# pcb.net
KiCad netlist of a schematic drawn in EAGLE
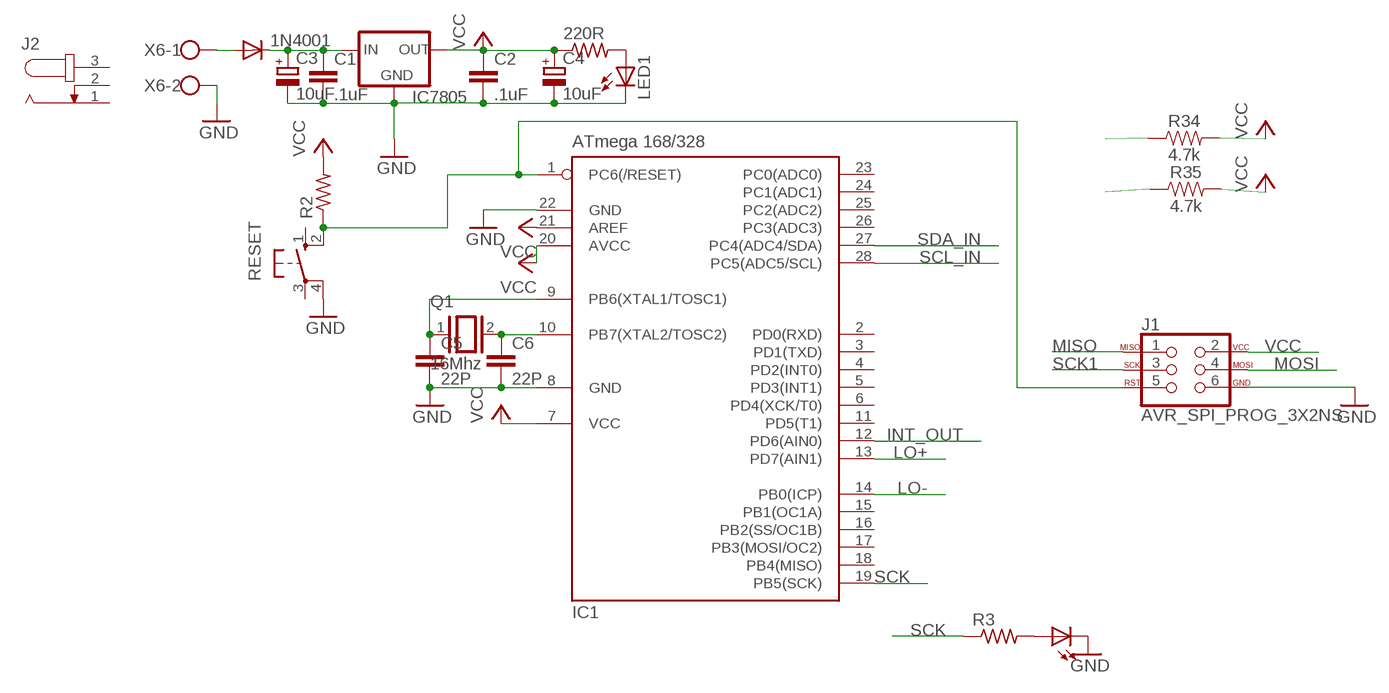
[diagram p0: schematic, sheet 1]
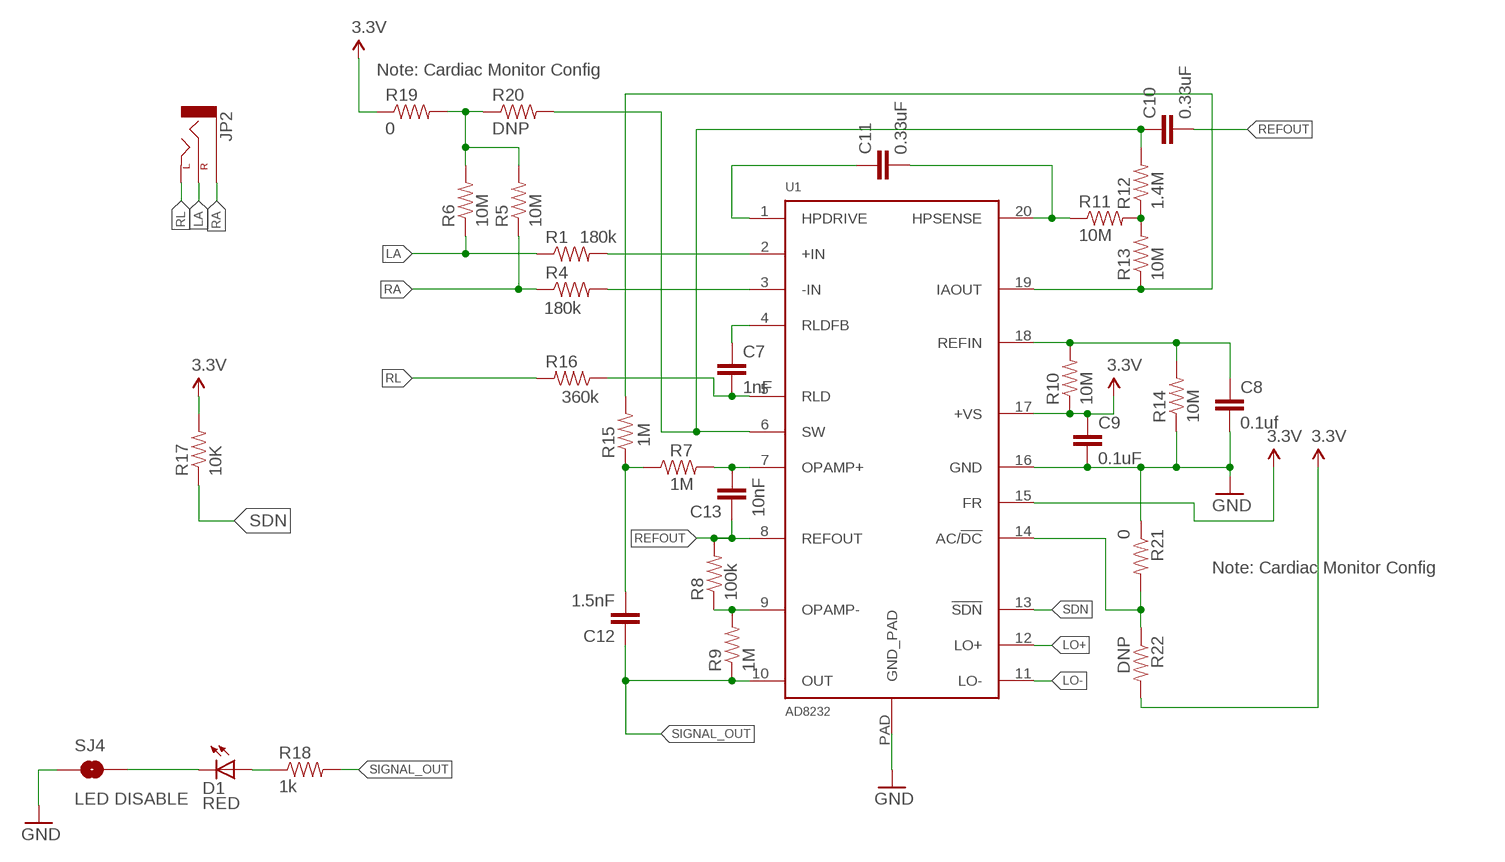
[diagram p1: schematic, sheet 2]
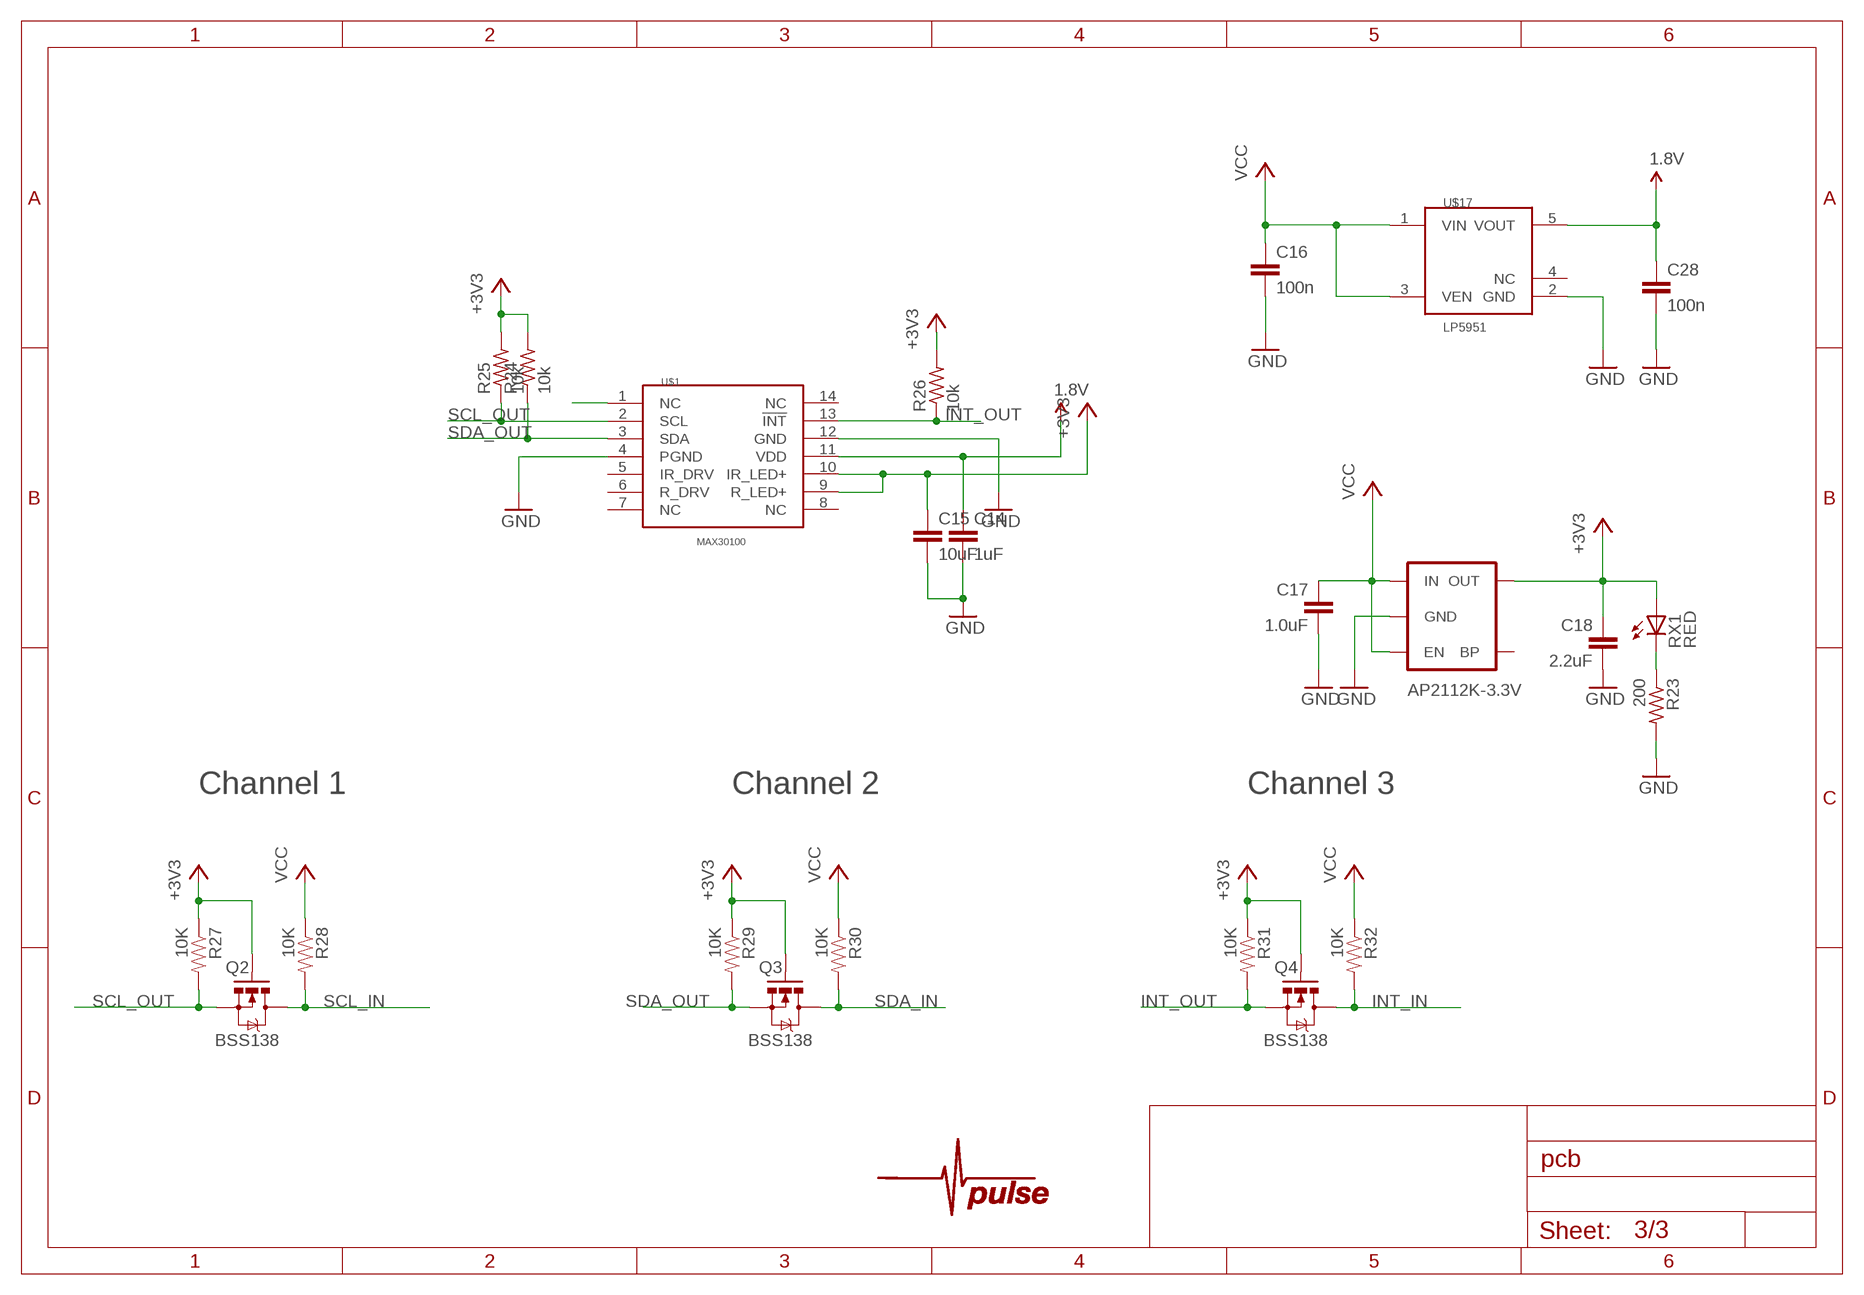
[diagram p2: schematic, sheet 3]

(export (version "E")
  (design (tool "Eeschema 10.0.6"))
  (components
    (comp (ref "C14")
      (value "1uF")
      (footprint "eagle-import:C0805")
      (libsource (lib "eagle-import") (part "C-EUC0805"))
    )
    (comp (ref "C15")
      (value "10uF")
      (footprint "eagle-import:C0805")
      (libsource (lib "eagle-import") (part "C-EUC0805"))
    )
    (comp (ref "C16")
      (value "100n")
      (footprint "eagle-import:C0402")
      (libsource (lib "eagle-import") (part "C-EUC0402"))
    )
    (comp (ref "C17")
      (value "1.0uF")
      (footprint "eagle-import:0805")
      (libsource (lib "eagle-import") (part "1.0UF-25V-+80/-20(0805)"))
    )
    (comp (ref "C18")
      (value "2.2uF")
      (footprint "eagle-import:C0805")
      (libsource (lib "eagle-import") (part "C-EUC0805"))
    )
    (comp (ref "C28")
      (value "100n")
      (footprint "eagle-import:C0402")
      (libsource (lib "eagle-import") (part "C-EUC0402"))
    )
    (comp (ref "Q2")
      (value "BSS138")
      (footprint "eagle-import:SOT23-3")
      (libsource (lib "eagle-import") (part "MOSFET-NCHANNELSMD"))
    )
    (comp (ref "Q3")
      (value "BSS138")
      (footprint "eagle-import:SOT23-3")
      (libsource (lib "eagle-import") (part "MOSFET-NCHANNELSMD"))
    )
    (comp (ref "Q4")
      (value "BSS138")
      (footprint "eagle-import:SOT23-3")
      (libsource (lib "eagle-import") (part "MOSFET-NCHANNELSMD"))
    )
    (comp (ref "R23")
      (value "200")
      (footprint "eagle-import:R0402")
      (libsource (lib "eagle-import") (part "R-US_R0402"))
    )
    (comp (ref "R24")
      (value "10k")
      (footprint "eagle-import:R0402")
      (libsource (lib "eagle-import") (part "R-US_R0402"))
    )
    (comp (ref "R25")
      (value "10k")
      (footprint "eagle-import:R0402")
      (libsource (lib "eagle-import") (part "R-US_R0402"))
    )
    (comp (ref "R26")
      (value "10k")
      (footprint "eagle-import:R0402")
      (libsource (lib "eagle-import") (part "R-US_R0402"))
    )
    (comp (ref "R27")
      (value "10K")
      (footprint "eagle-import:0402-RES")
      (libsource (lib "eagle-import") (part "RESISTOR0402-RES"))
    )
    (comp (ref "R28")
      (value "10K")
      (footprint "eagle-import:0402-RES")
      (libsource (lib "eagle-import") (part "RESISTOR0402-RES"))
    )
    (comp (ref "R29")
      (value "10K")
      (footprint "eagle-import:0402-RES")
      (libsource (lib "eagle-import") (part "RESISTOR0402-RES"))
    )
    (comp (ref "R30")
      (value "10K")
      (footprint "eagle-import:0402-RES")
      (libsource (lib "eagle-import") (part "RESISTOR0402-RES"))
    )
    (comp (ref "R31")
      (value "10K")
      (footprint "eagle-import:0402-RES")
      (libsource (lib "eagle-import") (part "RESISTOR0402-RES"))
    )
    (comp (ref "R32")
      (value "10K")
      (footprint "eagle-import:0402-RES")
      (libsource (lib "eagle-import") (part "RESISTOR0402-RES"))
    )
    (comp (ref "RX1")
      (value "RED")
      (footprint "eagle-import:CHIPLED_0603")
      (libsource (lib "eagle-import") (part "LEDCHIPLED_0603"))
    )
    (comp (ref "U$1")
      (value "MAX30100")
      (footprint "eagle-import:OESIP-14")
      (libsource (lib "eagle-import") (part "MAX30100"))
    )
    (comp (ref "U$3")
      (value "PROTY_LOGO_WITH_TEXT")
      (footprint "eagle-import:PROTY_WITH_TEXT")
      (libsource (lib "eagle-import") (part "PROTY_LOGO_WITH_TEXT"))
    )
    (comp (ref "U$4")
      (value "PULSE")
      (footprint "eagle-import:PULSE")
      (libsource (lib "eagle-import") (part "PULSE"))
    )
    (comp (ref "U$17")
      (value "LP5951")
      (footprint "eagle-import:SC70-5")
      (libsource (lib "eagle-import") (part "LP5951"))
    )
    (comp (ref "U2")
      (value "AP2112K-3.3V")
      (footprint "eagle-import:SOT23-5")
      (libsource (lib "eagle-import") (part "V_REG_LDOSMD"))
    )
    (comp (ref "1N4001")
      (value "BYT85")
      (footprint "eagle-import:DO220S")
      (libsource (lib "eagle-import") (part "BYT85"))
    )
    (comp (ref "220R")
      (value "R-US_0204/7")
      (footprint "eagle-import:0204_7")
      (libsource (lib "eagle-import") (part "R-US_0204/7"))
    )
    (comp (ref "C1")
      (value ".1uF")
      (footprint "eagle-import:C025-024X044")
      (libsource (lib "eagle-import") (part "C-EU025-024X044"))
    )
    (comp (ref "C2")
      (value ".1uF")
      (footprint "eagle-import:C025-024X044")
      (libsource (lib "eagle-import") (part "C-EU025-024X044"))
    )
    (comp (ref "C3")
      (value "10uF")
      (footprint "eagle-import:E1,8-4")
      (libsource (lib "eagle-import") (part "CPOL-EUE1.8-4"))
    )
    (comp (ref "C4")
      (value "10uF")
      (footprint "eagle-import:E1,8-4")
      (libsource (lib "eagle-import") (part "CPOL-EUE1.8-4"))
    )
    (comp (ref "C5")
      (value "22P")
      (footprint "eagle-import:C025-024X044")
      (libsource (lib "eagle-import") (part "C-EU025-024X044"))
    )
    (comp (ref "C6")
      (value "22P")
      (footprint "eagle-import:C025-024X044")
      (libsource (lib "eagle-import") (part "C-EU025-024X044"))
    )
    (comp (ref "IC1")
      (value "ATmega 168/328")
      (footprint "eagle-import:DIL28-3")
      (libsource (lib "eagle-import") (part "MEGA8-P"))
    )
    (comp (ref "IC7805")
      (value "78XXS")
      (footprint "eagle-import:78XXS")
      (libsource (lib "eagle-import") (part "78XXS"))
    )
    (comp (ref "J1")
      (value "AVR_SPI_PROG_3X2NS")
      (footprint "eagle-import:2X3-NS")
      (libsource (lib "eagle-import") (part "AVR_SPI_PROG_3X2NS"))
    )
    (comp (ref "J2")
      (value "JACK-PLUG0")
      (footprint "eagle-import:SPC4077")
      (libsource (lib "eagle-import") (part "JACK-PLUG0"))
    )
    (comp (ref "LED1")
      (value "LED3MM")
      (footprint "eagle-import:LED3MM")
      (libsource (lib "eagle-import") (part "LED3MM"))
    )
    (comp (ref "LED2")
      (value "LED3MM")
      (footprint "eagle-import:LED3MM")
      (libsource (lib "eagle-import") (part "LED3MM"))
    )
    (comp (ref "Q1")
      (value "16Mhz")
      (footprint "eagle-import:QS")
      (libsource (lib "eagle-import") (part "XTAL/S"))
    )
    (comp (ref "R2")
      (value "R-US_0204/7")
      (footprint "eagle-import:0204_7")
      (libsource (lib "eagle-import") (part "R-US_0204/7"))
    )
    (comp (ref "R3")
      (value "R-US_0204/7")
      (footprint "eagle-import:0204_7")
      (libsource (lib "eagle-import") (part "R-US_0204/7"))
    )
    (comp (ref "R34")
      (value "4.7k")
      (footprint "eagle-import:0603")
      (libsource (lib "eagle-import") (part "4.7KOHM-0603-1/10W-1%"))
    )
    (comp (ref "R35")
      (value "4.7k")
      (footprint "eagle-import:0603")
      (libsource (lib "eagle-import") (part "4.7KOHM-0603-1/10W-1%"))
    )
    (comp (ref "RESET")
      (value "10-XX")
      (footprint "eagle-import:B3F-10XX")
      (libsource (lib "eagle-import") (part "10-XX"))
    )
    (comp (ref "X6")
      (value "W237-102")
      (footprint "eagle-import:W237-102")
      (libsource (lib "eagle-import") (part "W237-102"))
    )
    (comp (ref "C7")
      (value "1nF")
      (footprint "eagle-import:0603-CAP")
      (libsource (lib "eagle-import") (part "CAP0603-CAP"))
    )
    (comp (ref "C8")
      (value "0.1uf")
      (footprint "eagle-import:0603-CAP")
      (libsource (lib "eagle-import") (part "CAP0603-CAP"))
    )
    (comp (ref "C9")
      (value "0.1uF")
      (footprint "eagle-import:0603-CAP")
      (libsource (lib "eagle-import") (part "CAP0603-CAP"))
    )
    (comp (ref "C10")
      (value "0.33uF")
      (footprint "eagle-import:0805")
      (libsource (lib "eagle-import") (part "CAP0805"))
    )
    (comp (ref "C11")
      (value "0.33uF")
      (footprint "eagle-import:0805")
      (libsource (lib "eagle-import") (part "CAP0805"))
    )
    (comp (ref "C12")
      (value "1.5nF")
      (footprint "eagle-import:0603-CAP")
      (libsource (lib "eagle-import") (part "CAP0603-CAP"))
    )
    (comp (ref "C13")
      (value "10nF")
      (footprint "eagle-import:0603-CAP")
      (libsource (lib "eagle-import") (part "CAP0603-CAP"))
    )
    (comp (ref "D1")
      (value "RED")
      (footprint "eagle-import:LED-0603")
      (libsource (lib "eagle-import") (part "LED-RED0603"))
    )
    (comp (ref "JP2")
      (value "AUDIO-JACKSMD2")
      (footprint "eagle-import:AUDIO-JACK-3.5MM-SMD")
      (libsource (lib "eagle-import") (part "AUDIO-JACKSMD2"))
    )
    (comp (ref "R1")
      (value "180k")
      (footprint "eagle-import:0603-RES")
      (libsource (lib "eagle-import") (part "SparkFun-Passives_RESISTOR0603-RES"))
    )
    (comp (ref "R4")
      (value "180k")
      (footprint "eagle-import:0603-RES")
      (libsource (lib "eagle-import") (part "SparkFun-Passives_RESISTOR0603-RES"))
    )
    (comp (ref "R5")
      (value "10M")
      (footprint "eagle-import:0603-RES")
      (libsource (lib "eagle-import") (part "SparkFun-Passives_RESISTOR0603-RES"))
    )
    (comp (ref "R6")
      (value "10M")
      (footprint "eagle-import:0603-RES")
      (libsource (lib "eagle-import") (part "SparkFun-Passives_RESISTOR0603-RES"))
    )
    (comp (ref "R7")
      (value "1M")
      (footprint "eagle-import:0603-RES")
      (libsource (lib "eagle-import") (part "SparkFun-Passives_RESISTOR0603-RES"))
    )
    (comp (ref "R8")
      (value "100k")
      (footprint "eagle-import:0603-RES")
      (libsource (lib "eagle-import") (part "SparkFun-Passives_RESISTOR0603-RES"))
    )
    (comp (ref "R9")
      (value "1M")
      (footprint "eagle-import:0603-RES")
      (libsource (lib "eagle-import") (part "SparkFun-Passives_RESISTOR0603-RES"))
    )
    (comp (ref "R10")
      (value "10M")
      (footprint "eagle-import:0603-RES")
      (libsource (lib "eagle-import") (part "SparkFun-Passives_RESISTOR0603-RES"))
    )
    (comp (ref "R11")
      (value "10M")
      (footprint "eagle-import:0603-RES")
      (libsource (lib "eagle-import") (part "SparkFun-Passives_RESISTOR0603-RES"))
    )
    (comp (ref "R12")
      (value "1.4M")
      (footprint "eagle-import:0603-RES")
      (libsource (lib "eagle-import") (part "SparkFun-Passives_RESISTOR0603-RES"))
    )
    (comp (ref "R13")
      (value "10M")
      (footprint "eagle-import:0603-RES")
      (libsource (lib "eagle-import") (part "SparkFun-Passives_RESISTOR0603-RES"))
    )
    (comp (ref "R14")
      (value "10M")
      (footprint "eagle-import:0603-RES")
      (libsource (lib "eagle-import") (part "SparkFun-Passives_RESISTOR0603-RES"))
    )
    (comp (ref "R15")
      (value "1M")
      (footprint "eagle-import:0603-RES")
      (libsource (lib "eagle-import") (part "SparkFun-Passives_RESISTOR0603-RES"))
    )
    (comp (ref "R16")
      (value "360k")
      (footprint "eagle-import:0603-RES")
      (libsource (lib "eagle-import") (part "SparkFun-Passives_RESISTOR0603-RES"))
    )
    (comp (ref "R17")
      (value "10K")
      (footprint "eagle-import:0603-RES")
      (libsource (lib "eagle-import") (part "10KOHM1/10W1%(0603)0603"))
    )
    (comp (ref "R18")
      (value "1k")
      (footprint "eagle-import:0603-RES")
      (libsource (lib "eagle-import") (part "1K-1%"))
    )
    (comp (ref "R19")
      (value "0")
      (footprint "eagle-import:0603")
      (libsource (lib "eagle-import") (part "0OHM1/10W5%(0603)"))
    )
    (comp (ref "R20")
      (value "DNP")
      (footprint "eagle-import:0603")
      (libsource (lib "eagle-import") (part "0OHM1/10W5%(0603)"))
    )
    (comp (ref "R21")
      (value "0")
      (footprint "eagle-import:0603")
      (libsource (lib "eagle-import") (part "0OHM1/10W5%(0603)"))
    )
    (comp (ref "R22")
      (value "DNP")
      (footprint "eagle-import:0603")
      (libsource (lib "eagle-import") (part "0OHM1/10W5%(0603)"))
    )
    (comp (ref "SJ4")
      (value "LED DISABLE")
      (footprint "eagle-import:SJ_2S-TRACE")
      (libsource (lib "eagle-import") (part "SOLDERJUMPERTRACE"))
    )
    (comp (ref "U1")
      (value "AD8232")
      (footprint "eagle-import:LFCSP_20")
      (libsource (lib "eagle-import") (part "AD8232"))
    )
  )
  (nets
    (net (code "1") (name "+3V3") (class "Default")
      (node (ref "C15") (pin "1") (pinfunction "1_1") (pintype "passive"))
      (node (ref "C18") (pin "1") (pinfunction "1_1") (pintype "passive"))
      (node (ref "Q2") (pin "1") (pinfunction "G_1") (pintype "passive"))
      (node (ref "Q3") (pin "1") (pinfunction "G_1") (pintype "passive"))
      (node (ref "Q4") (pin "1") (pinfunction "G_1") (pintype "passive"))
      (node (ref "R24") (pin "2") (pinfunction "2_2") (pintype "passive"))
      (node (ref "R25") (pin "2") (pinfunction "2_2") (pintype "passive"))
      (node (ref "R26") (pin "2") (pinfunction "2_2") (pintype "passive"))
      (node (ref "R27") (pin "1") (pinfunction "1_1") (pintype "passive"))
      (node (ref "R29") (pin "1") (pinfunction "1_1") (pintype "passive"))
      (node (ref "R31") (pin "1") (pinfunction "1_1") (pintype "passive"))
      (node (ref "RX1") (pin "A") (pinfunction "A_A") (pintype "passive"))
      (node (ref "U$1") (pin "10") (pinfunction "IR_LED+_10") (pintype "bidirectional"))
      (node (ref "U$1") (pin "9") (pinfunction "R_LED+_9") (pintype "bidirectional"))
      (node (ref "U2") (pin "5") (pinfunction "OUT_5") (pintype "passive"))
    )
    (net (code "2") (name "1.8V") (class "Default")
      (node (ref "C14") (pin "1") (pinfunction "1_1") (pintype "passive"))
      (node (ref "C28") (pin "1") (pinfunction "1_1") (pintype "passive"))
      (node (ref "U$1") (pin "11") (pinfunction "VDD_11") (pintype "bidirectional"))
      (node (ref "U$17") (pin "5") (pinfunction "VOUT_5") (pintype "bidirectional"))
    )
    (net (code "3") (name "3.3V") (class "Default")
      (node (ref "C9") (pin "1") (pinfunction "1_1") (pintype "passive"))
      (node (ref "R10") (pin "1") (pinfunction "1_1") (pintype "passive"))
      (node (ref "R17") (pin "2") (pinfunction "2_2") (pintype "passive"))
      (node (ref "R19") (pin "1") (pinfunction "1_1") (pintype "passive"))
      (node (ref "R22") (pin "2") (pinfunction "2_2") (pintype "passive"))
      (node (ref "U1") (pin "15") (pinfunction "FR_15") (pintype "bidirectional"))
      (node (ref "U1") (pin "17") (pinfunction "+VS_17") (pintype "bidirectional"))
    )
    (net (code "4") (name "GND") (class "Default")
      (node (ref "C1") (pin "2") (pinfunction "2_2") (pintype "passive"))
      (node (ref "C14") (pin "2") (pinfunction "2_2") (pintype "passive"))
      (node (ref "C15") (pin "2") (pinfunction "2_2") (pintype "passive"))
      (node (ref "C16") (pin "2") (pinfunction "2_2") (pintype "passive"))
      (node (ref "C17") (pin "2") (pinfunction "2_2") (pintype "passive"))
      (node (ref "C18") (pin "2") (pinfunction "2_2") (pintype "passive"))
      (node (ref "C2") (pin "2") (pinfunction "2_2") (pintype "passive"))
      (node (ref "C28") (pin "2") (pinfunction "2_2") (pintype "passive"))
      (node (ref "C3") (pin "-") (pinfunction "-_-") (pintype "passive"))
      (node (ref "C4") (pin "-") (pinfunction "-_-") (pintype "passive"))
      (node (ref "C5") (pin "2") (pinfunction "2_2") (pintype "passive"))
      (node (ref "C6") (pin "2") (pinfunction "2_2") (pintype "passive"))
      (node (ref "C8") (pin "2") (pinfunction "2_2") (pintype "passive"))
      (node (ref "C9") (pin "2") (pinfunction "2_2") (pintype "passive"))
      (node (ref "IC1") (pin "22") (pinfunction "GND_22") (pintype "power_in"))
      (node (ref "IC1") (pin "8") (pinfunction "GND_8") (pintype "power_in"))
      (node (ref "IC7805") (pin "GND") (pinfunction "GND_GND") (pintype "input"))
      (node (ref "J1") (pin "6") (pinfunction "6_6") (pintype "passive"))
      (node (ref "LED1") (pin "K") (pinfunction "C_K") (pintype "passive"))
      (node (ref "LED2") (pin "K") (pinfunction "C_K") (pintype "passive"))
      (node (ref "R14") (pin "1") (pinfunction "1_1") (pintype "passive"))
      (node (ref "R21") (pin "1") (pinfunction "1_1") (pintype "passive"))
      (node (ref "R23") (pin "2") (pinfunction "2_2") (pintype "passive"))
      (node (ref "RESET") (pin "4") (pinfunction "P1_4") (pintype "passive"))
      (node (ref "SJ4") (pin "1") (pinfunction "1_1") (pintype "passive"))
      (node (ref "U$1") (pin "12") (pinfunction "GND_12") (pintype "bidirectional"))
      (node (ref "U$1") (pin "4") (pinfunction "PGND_4") (pintype "bidirectional"))
      (node (ref "U$17") (pin "2") (pinfunction "GND_2") (pintype "bidirectional"))
      (node (ref "U1") (pin "16") (pinfunction "GND_16") (pintype "bidirectional"))
      (node (ref "U1") (pin "PAD") (pinfunction "GND_PAD_PAD") (pintype "bidirectional"))
      (node (ref "U2") (pin "2") (pinfunction "GND_2") (pintype "input"))
      (node (ref "X6") (pin "2") (pinfunction "KL_2") (pintype "passive"))
    )
    (net (code "5") (name "INT_IN") (class "Default")
      (node (ref "Q4") (pin "3") (pinfunction "D_3") (pintype "passive"))
      (node (ref "R32") (pin "2") (pinfunction "2_2") (pintype "passive"))
    )
    (net (code "6") (name "INT_OUT") (class "Default")
      (node (ref "IC1") (pin "12") (pinfunction "PD6(AIN0)_12") (pintype "bidirectional"))
      (node (ref "Q4") (pin "2") (pinfunction "S_2") (pintype "passive"))
      (node (ref "R26") (pin "1") (pinfunction "1_1") (pintype "passive"))
      (node (ref "R31") (pin "2") (pinfunction "2_2") (pintype "passive"))
      (node (ref "U$1") (pin "13") (pinfunction "~{INT}_13") (pintype "bidirectional"))
    )
    (net (code "7") (name "LA") (class "Default")
      (node (ref "JP2") (pin "RING") (pinfunction "RIGHT_RING") (pintype "bidirectional"))
      (node (ref "R1") (pin "1") (pinfunction "1_1") (pintype "passive"))
      (node (ref "R6") (pin "1") (pinfunction "1_1") (pintype "passive"))
    )
    (net (code "8") (name "LO+") (class "Default")
      (node (ref "IC1") (pin "13") (pinfunction "PD7(AIN1)_13") (pintype "bidirectional"))
      (node (ref "U1") (pin "12") (pinfunction "LO+_12") (pintype "bidirectional"))
    )
    (net (code "9") (name "LO-") (class "Default")
      (node (ref "IC1") (pin "14") (pinfunction "PB0(ICP)_14") (pintype "bidirectional"))
      (node (ref "U1") (pin "11") (pinfunction "LO-_11") (pintype "bidirectional"))
    )
    (net (code "10") (name "MISO") (class "Default")
      (node (ref "J1") (pin "1") (pinfunction "1_1") (pintype "passive"))
    )
    (net (code "11") (name "MOSI") (class "Default")
      (node (ref "J1") (pin "4") (pinfunction "4_4") (pintype "passive"))
    )
    (net (code "12") (name "Net-(1N4001-PadC)") (class "Default")
      (node (ref "1N4001") (pin "C") (pinfunction "C_C") (pintype "passive"))
      (node (ref "C1") (pin "1") (pinfunction "1_1") (pintype "passive"))
      (node (ref "C3") (pin "+") (pinfunction "+_+") (pintype "passive"))
      (node (ref "IC7805") (pin "IN") (pinfunction "IN_IN") (pintype "input"))
    )
    (net (code "13") (name "Net-(220R-Pad2)") (class "Default")
      (node (ref "220R") (pin "2") (pinfunction "2_2") (pintype "passive"))
      (node (ref "LED1") (pin "A") (pinfunction "A_A") (pintype "passive"))
    )
    (net (code "14") (name "Net-(C12-Pad2)") (class "Default")
      (node (ref "C12") (pin "2") (pinfunction "2_2") (pintype "passive"))
      (node (ref "R15") (pin "1") (pinfunction "1_1") (pintype "passive"))
      (node (ref "R7") (pin "1") (pinfunction "1_1") (pintype "passive"))
    )
    (net (code "15") (name "Net-(D1-PadA)") (class "Default")
      (node (ref "D1") (pin "A") (pinfunction "A_A") (pintype "passive"))
      (node (ref "R18") (pin "1") (pinfunction "1_1") (pintype "passive"))
    )
    (net (code "16") (name "Net-(D1-PadC)") (class "Default")
      (node (ref "D1") (pin "C") (pinfunction "C_C") (pintype "passive"))
      (node (ref "SJ4") (pin "2") (pinfunction "2_2") (pintype "passive"))
    )
    (net (code "17") (name "Net-(IC1-PB6(XTAL1{slash}TOSC1))") (class "Default")
      (node (ref "C5") (pin "1") (pinfunction "1_1") (pintype "passive"))
      (node (ref "IC1") (pin "9") (pinfunction "PB6(XTAL1/TOSC1)_9") (pintype "bidirectional"))
      (node (ref "Q1") (pin "1") (pinfunction "1_1") (pintype "passive"))
    )
    (net (code "18") (name "Net-(IC1-PB7(XTAL2{slash}TOSC2))") (class "Default")
      (node (ref "C6") (pin "1") (pinfunction "1_1") (pintype "passive"))
      (node (ref "IC1") (pin "10") (pinfunction "PB7(XTAL2/TOSC2)_10") (pintype "bidirectional"))
      (node (ref "Q1") (pin "2") (pinfunction "2_2") (pintype "passive"))
    )
    (net (code "19") (name "Net-(IC1-PC6({slash}RESET))") (class "Default")
      (node (ref "IC1") (pin "1") (pinfunction "PC6(/RESET)_1") (pintype "bidirectional"))
      (node (ref "J1") (pin "5") (pinfunction "5_5") (pintype "passive"))
      (node (ref "R2") (pin "1") (pinfunction "1_1") (pintype "passive"))
      (node (ref "RESET") (pin "2") (pinfunction "S1_2") (pintype "passive"))
    )
    (net (code "20") (name "Net-(LED2-PadA)") (class "Default")
      (node (ref "LED2") (pin "A") (pinfunction "A_A") (pintype "passive"))
      (node (ref "R3") (pin "2") (pinfunction "2_2") (pintype "passive"))
    )
    (net (code "21") (name "Net-(R11-Pad2)") (class "Default")
      (node (ref "R11") (pin "2") (pinfunction "2_2") (pintype "passive"))
      (node (ref "R12") (pin "1") (pinfunction "1_1") (pintype "passive"))
      (node (ref "R13") (pin "2") (pinfunction "2_2") (pintype "passive"))
    )
    (net (code "22") (name "Net-(R19-Pad2)") (class "Default")
      (node (ref "R19") (pin "2") (pinfunction "2_2") (pintype "passive"))
      (node (ref "R20") (pin "1") (pinfunction "1_1") (pintype "passive"))
      (node (ref "R5") (pin "2") (pinfunction "2_2") (pintype "passive"))
      (node (ref "R6") (pin "2") (pinfunction "2_2") (pintype "passive"))
    )
    (net (code "23") (name "Net-(R23-Pad1)") (class "Default")
      (node (ref "R23") (pin "1") (pinfunction "1_1") (pintype "passive"))
      (node (ref "RX1") (pin "C") (pinfunction "C_C") (pintype "passive"))
    )
    (net (code "24") (name "Net-(U1-+IN)") (class "Default")
      (node (ref "R1") (pin "2") (pinfunction "2_2") (pintype "passive"))
      (node (ref "U1") (pin "2") (pinfunction "+IN_2") (pintype "bidirectional"))
    )
    (net (code "25") (name "Net-(U1--IN)") (class "Default")
      (node (ref "R4") (pin "2") (pinfunction "2_2") (pintype "passive"))
      (node (ref "U1") (pin "3") (pinfunction "-IN_3") (pintype "bidirectional"))
    )
    (net (code "26") (name "Net-(U1-AC{slash}~{DC})") (class "Default")
      (node (ref "R21") (pin "2") (pinfunction "2_2") (pintype "passive"))
      (node (ref "R22") (pin "1") (pinfunction "1_1") (pintype "passive"))
      (node (ref "U1") (pin "14") (pinfunction "AC/~{DC}_14") (pintype "bidirectional"))
    )
    (net (code "27") (name "Net-(U1-HPDRIVE)") (class "Default")
      (node (ref "C11") (pin "1") (pinfunction "1_1") (pintype "passive"))
      (node (ref "U1") (pin "1") (pinfunction "HPDRIVE_1") (pintype "bidirectional"))
    )
    (net (code "28") (name "Net-(U1-HPSENSE)") (class "Default")
      (node (ref "C11") (pin "2") (pinfunction "2_2") (pintype "passive"))
      (node (ref "R11") (pin "1") (pinfunction "1_1") (pintype "passive"))
      (node (ref "U1") (pin "20") (pinfunction "HPSENSE_20") (pintype "bidirectional"))
    )
    (net (code "29") (name "Net-(U1-IAOUT)") (class "Default")
      (node (ref "R13") (pin "1") (pinfunction "1_1") (pintype "passive"))
      (node (ref "R15") (pin "2") (pinfunction "2_2") (pintype "passive"))
      (node (ref "U1") (pin "19") (pinfunction "IAOUT_19") (pintype "bidirectional"))
    )
    (net (code "30") (name "Net-(U1-OPAMP+)") (class "Default")
      (node (ref "C13") (pin "2") (pinfunction "2_2") (pintype "passive"))
      (node (ref "R7") (pin "2") (pinfunction "2_2") (pintype "passive"))
      (node (ref "U1") (pin "7") (pinfunction "OPAMP+_7") (pintype "bidirectional"))
    )
    (net (code "31") (name "Net-(U1-OPAMP-)") (class "Default")
      (node (ref "R8") (pin "1") (pinfunction "1_1") (pintype "passive"))
      (node (ref "R9") (pin "2") (pinfunction "2_2") (pintype "passive"))
      (node (ref "U1") (pin "9") (pinfunction "OPAMP-_9") (pintype "bidirectional"))
    )
    (net (code "32") (name "Net-(U1-REFIN)") (class "Default")
      (node (ref "C8") (pin "1") (pinfunction "1_1") (pintype "passive"))
      (node (ref "R10") (pin "2") (pinfunction "2_2") (pintype "passive"))
      (node (ref "R14") (pin "2") (pinfunction "2_2") (pintype "passive"))
      (node (ref "U1") (pin "18") (pinfunction "REFIN_18") (pintype "bidirectional"))
    )
    (net (code "33") (name "Net-(U1-RLD)") (class "Default")
      (node (ref "C7") (pin "2") (pinfunction "2_2") (pintype "passive"))
      (node (ref "R16") (pin "1") (pinfunction "1_1") (pintype "passive"))
      (node (ref "U1") (pin "5") (pinfunction "RLD_5") (pintype "bidirectional"))
    )
    (net (code "34") (name "Net-(U1-RLDFB)") (class "Default")
      (node (ref "C7") (pin "1") (pinfunction "1_1") (pintype "passive"))
      (node (ref "U1") (pin "4") (pinfunction "RLDFB_4") (pintype "bidirectional"))
    )
    (net (code "35") (name "Net-(U1-SW)") (class "Default")
      (node (ref "C10") (pin "1") (pinfunction "1_1") (pintype "passive"))
      (node (ref "R12") (pin "2") (pinfunction "2_2") (pintype "passive"))
      (node (ref "R20") (pin "2") (pinfunction "2_2") (pintype "passive"))
      (node (ref "U1") (pin "6") (pinfunction "SW_6") (pintype "bidirectional"))
    )
    (net (code "36") (name "Net-(U2-EN)") (class "Default")
      (node (ref "C17") (pin "1") (pinfunction "1_1") (pintype "passive"))
      (node (ref "U2") (pin "1") (pinfunction "IN_1") (pintype "input"))
      (node (ref "U2") (pin "3") (pinfunction "EN_3") (pintype "input"))
    )
    (net (code "37") (name "Net-(X6A-KL)") (class "Default")
      (node (ref "1N4001") (pin "A") (pinfunction "A_A") (pintype "passive"))
      (node (ref "X6") (pin "1") (pinfunction "KL_1") (pintype "passive"))
    )
    (net (code "38") (name "RA") (class "Default")
      (node (ref "JP2") (pin "SLEEVE") (pinfunction "SLEEVE_SLEEVE") (pintype "bidirectional"))
      (node (ref "R4") (pin "1") (pinfunction "1_1") (pintype "passive"))
      (node (ref "R5") (pin "1") (pinfunction "1_1") (pintype "passive"))
    )
    (net (code "39") (name "REFOUT") (class "Default")
      (node (ref "C10") (pin "2") (pinfunction "2_2") (pintype "passive"))
      (node (ref "C13") (pin "1") (pinfunction "1_1") (pintype "passive"))
      (node (ref "R8") (pin "2") (pinfunction "2_2") (pintype "passive"))
      (node (ref "U1") (pin "8") (pinfunction "REFOUT_8") (pintype "bidirectional"))
    )
    (net (code "40") (name "RL") (class "Default")
      (node (ref "JP2") (pin "TIP") (pinfunction "LEFT_TIP") (pintype "bidirectional"))
      (node (ref "R16") (pin "2") (pinfunction "2_2") (pintype "passive"))
    )
    (net (code "41") (name "SCK") (class "Default")
      (node (ref "IC1") (pin "19") (pinfunction "PB5(SCK)_19") (pintype "bidirectional"))
      (node (ref "R3") (pin "1") (pinfunction "1_1") (pintype "passive"))
    )
    (net (code "42") (name "SCK1") (class "Default")
      (node (ref "J1") (pin "3") (pinfunction "3_3") (pintype "passive"))
    )
    (net (code "43") (name "SCL_IN") (class "Default")
      (node (ref "IC1") (pin "28") (pinfunction "PC5(ADC5/SCL)_28") (pintype "bidirectional"))
      (node (ref "Q2") (pin "3") (pinfunction "D_3") (pintype "passive"))
      (node (ref "R28") (pin "2") (pinfunction "2_2") (pintype "passive"))
    )
    (net (code "44") (name "SCL_OUT") (class "Default")
      (node (ref "Q2") (pin "2") (pinfunction "S_2") (pintype "passive"))
      (node (ref "R25") (pin "1") (pinfunction "1_1") (pintype "passive"))
      (node (ref "R27") (pin "2") (pinfunction "2_2") (pintype "passive"))
      (node (ref "U$1") (pin "2") (pinfunction "SCL_2") (pintype "bidirectional"))
    )
    (net (code "45") (name "SDA_IN") (class "Default")
      (node (ref "IC1") (pin "27") (pinfunction "PC4(ADC4/SDA)_27") (pintype "bidirectional"))
      (node (ref "Q3") (pin "3") (pinfunction "D_3") (pintype "passive"))
      (node (ref "R30") (pin "2") (pinfunction "2_2") (pintype "passive"))
    )
    (net (code "46") (name "SDA_OUT") (class "Default")
      (node (ref "Q3") (pin "2") (pinfunction "S_2") (pintype "passive"))
      (node (ref "R24") (pin "1") (pinfunction "1_1") (pintype "passive"))
      (node (ref "R29") (pin "2") (pinfunction "2_2") (pintype "passive"))
      (node (ref "U$1") (pin "3") (pinfunction "SDA_3") (pintype "bidirectional"))
    )
    (net (code "47") (name "SDN") (class "Default")
      (node (ref "R17") (pin "1") (pinfunction "1_1") (pintype "passive"))
      (node (ref "U1") (pin "13") (pinfunction "~{SDN}_13") (pintype "bidirectional"))
    )
    (net (code "48") (name "SIGNAL_OUT") (class "Default")
      (node (ref "C12") (pin "1") (pinfunction "1_1") (pintype "passive"))
      (node (ref "R18") (pin "2") (pinfunction "2_2") (pintype "passive"))
      (node (ref "R9") (pin "1") (pinfunction "1_1") (pintype "passive"))
      (node (ref "U1") (pin "10") (pinfunction "OUT_10") (pintype "bidirectional"))
    )
    (net (code "49") (name "VCC") (class "Default")
      (node (ref "220R") (pin "1") (pinfunction "1_1") (pintype "passive"))
      (node (ref "C16") (pin "1") (pinfunction "1_1") (pintype "passive"))
      (node (ref "C2") (pin "1") (pinfunction "1_1") (pintype "passive"))
      (node (ref "C4") (pin "+") (pinfunction "+_+") (pintype "passive"))
      (node (ref "IC1") (pin "20") (pinfunction "AVCC_20") (pintype "power_in"))
      (node (ref "IC1") (pin "21") (pinfunction "AREF_21") (pintype "passive"))
      (node (ref "IC1") (pin "7") (pinfunction "VCC_7") (pintype "power_in"))
      (node (ref "IC7805") (pin "OUT") (pinfunction "OUT_OUT") (pintype "passive"))
      (node (ref "J1") (pin "2") (pinfunction "2_2") (pintype "passive"))
      (node (ref "R2") (pin "2") (pinfunction "2_2") (pintype "passive"))
      (node (ref "R28") (pin "1") (pinfunction "1_1") (pintype "passive"))
      (node (ref "R30") (pin "1") (pinfunction "1_1") (pintype "passive"))
      (node (ref "R32") (pin "1") (pinfunction "1_1") (pintype "passive"))
      (node (ref "R34") (pin "2") (pinfunction "2_2") (pintype "passive"))
      (node (ref "R35") (pin "2") (pinfunction "2_2") (pintype "passive"))
      (node (ref "U$17") (pin "1") (pinfunction "VIN_1") (pintype "bidirectional"))
      (node (ref "U$17") (pin "3") (pinfunction "VEN_3") (pintype "bidirectional"))
    )
    (net (code "50") (name "unconnected-(IC1-PB1(OC1A)-Pad15)") (class "Default")
      (node (ref "IC1") (pin "15") (pinfunction "PB1(OC1A)_15") (pintype "bidirectional"))
    )
    (net (code "51") (name "unconnected-(IC1-PB2(SS{slash}OC1B)-Pad16)") (class "Default")
      (node (ref "IC1") (pin "16") (pinfunction "PB2(SS/OC1B)_16") (pintype "bidirectional"))
    )
    (net (code "52") (name "unconnected-(IC1-PB3(MOSI{slash}OC2)-Pad17)") (class "Default")
      (node (ref "IC1") (pin "17") (pinfunction "PB3(MOSI/OC2)_17") (pintype "bidirectional"))
    )
    (net (code "53") (name "unconnected-(IC1-PB4(MISO)-Pad18)") (class "Default")
      (node (ref "IC1") (pin "18") (pinfunction "PB4(MISO)_18") (pintype "bidirectional"))
    )
    (net (code "54") (name "unconnected-(IC1-PC0(ADC0)-Pad23)") (class "Default")
      (node (ref "IC1") (pin "23") (pinfunction "PC0(ADC0)_23") (pintype "bidirectional"))
    )
    (net (code "55") (name "unconnected-(IC1-PC1(ADC1)-Pad24)") (class "Default")
      (node (ref "IC1") (pin "24") (pinfunction "PC1(ADC1)_24") (pintype "bidirectional"))
    )
    (net (code "56") (name "unconnected-(IC1-PC2(ADC2)-Pad25)") (class "Default")
      (node (ref "IC1") (pin "25") (pinfunction "PC2(ADC2)_25") (pintype "bidirectional"))
    )
    (net (code "57") (name "unconnected-(IC1-PC3(ADC3)-Pad26)") (class "Default")
      (node (ref "IC1") (pin "26") (pinfunction "PC3(ADC3)_26") (pintype "bidirectional"))
    )
    (net (code "58") (name "unconnected-(IC1-PD0(RXD)-Pad2)") (class "Default")
      (node (ref "IC1") (pin "2") (pinfunction "PD0(RXD)_2") (pintype "bidirectional"))
    )
    (net (code "59") (name "unconnected-(IC1-PD1(TXD)-Pad3)") (class "Default")
      (node (ref "IC1") (pin "3") (pinfunction "PD1(TXD)_3") (pintype "bidirectional"))
    )
    (net (code "60") (name "unconnected-(IC1-PD2(INT0)-Pad4)") (class "Default")
      (node (ref "IC1") (pin "4") (pinfunction "PD2(INT0)_4") (pintype "bidirectional"))
    )
    (net (code "61") (name "unconnected-(IC1-PD3(INT1)-Pad5)") (class "Default")
      (node (ref "IC1") (pin "5") (pinfunction "PD3(INT1)_5") (pintype "bidirectional"))
    )
    (net (code "62") (name "unconnected-(IC1-PD4(XCK{slash}T0)-Pad6)") (class "Default")
      (node (ref "IC1") (pin "6") (pinfunction "PD4(XCK/T0)_6") (pintype "bidirectional"))
    )
    (net (code "63") (name "unconnected-(IC1-PD5(T1)-Pad11)") (class "Default")
      (node (ref "IC1") (pin "11") (pinfunction "PD5(T1)_11") (pintype "bidirectional"))
    )
    (net (code "64") (name "unconnected-(J2-Pad1)") (class "Default")
      (node (ref "J2") (pin "1") (pinfunction "1_1") (pintype "passive"))
    )
    (net (code "65") (name "unconnected-(J2-Pad2)") (class "Default")
      (node (ref "J2") (pin "2") (pinfunction "2_2") (pintype "passive"))
    )
    (net (code "66") (name "unconnected-(J2-Pad3)") (class "Default")
      (node (ref "J2") (pin "3") (pinfunction "3_3") (pintype "passive"))
    )
    (net (code "67") (name "unconnected-(R34-Pad1)") (class "Default")
      (node (ref "R34") (pin "1") (pinfunction "1_1") (pintype "passive"))
    )
    (net (code "68") (name "unconnected-(R35-Pad1)") (class "Default")
      (node (ref "R35") (pin "1") (pinfunction "1_1") (pintype "passive"))
    )
    (net (code "69") (name "unconnected-(RESET-P-Pad3)") (class "Default")
      (node (ref "RESET") (pin "3") (pinfunction "P_3") (pintype "passive"))
    )
    (net (code "70") (name "unconnected-(RESET-S-Pad1)") (class "Default")
      (node (ref "RESET") (pin "1") (pinfunction "S_1") (pintype "passive"))
    )
    (net (code "71") (name "unconnected-(U$1-IR_DRV-Pad5)") (class "Default")
      (node (ref "U$1") (pin "5") (pinfunction "IR_DRV_5") (pintype "bidirectional"))
    )
    (net (code "72") (name "unconnected-(U$1-NC-Pad1)") (class "Default")
      (node (ref "U$1") (pin "1") (pinfunction "NC_1") (pintype "bidirectional"))
    )
    (net (code "73") (name "unconnected-(U$1-NC-Pad7)") (class "Default")
      (node (ref "U$1") (pin "7") (pinfunction "NC_7") (pintype "bidirectional"))
    )
    (net (code "74") (name "unconnected-(U$1-NC-Pad8)") (class "Default")
      (node (ref "U$1") (pin "8") (pinfunction "NC_8") (pintype "bidirectional"))
    )
    (net (code "75") (name "unconnected-(U$1-NC-Pad14)") (class "Default")
      (node (ref "U$1") (pin "14") (pinfunction "NC_14") (pintype "bidirectional"))
    )
    (net (code "76") (name "unconnected-(U$1-R_DRV-Pad6)") (class "Default")
      (node (ref "U$1") (pin "6") (pinfunction "R_DRV_6") (pintype "bidirectional"))
    )
    (net (code "77") (name "unconnected-(U$17-NC-Pad4)") (class "Default")
      (node (ref "U$17") (pin "4") (pinfunction "NC_4") (pintype "bidirectional"))
    )
    (net (code "78") (name "unconnected-(U2-BP-Pad4)") (class "Default")
      (node (ref "U2") (pin "4") (pinfunction "BP_4") (pintype "input"))
    )
  )
)
